# HYDRA_V4_ACTUATOR.net
KiCad netlist of a schematic drawn in Altium Designer
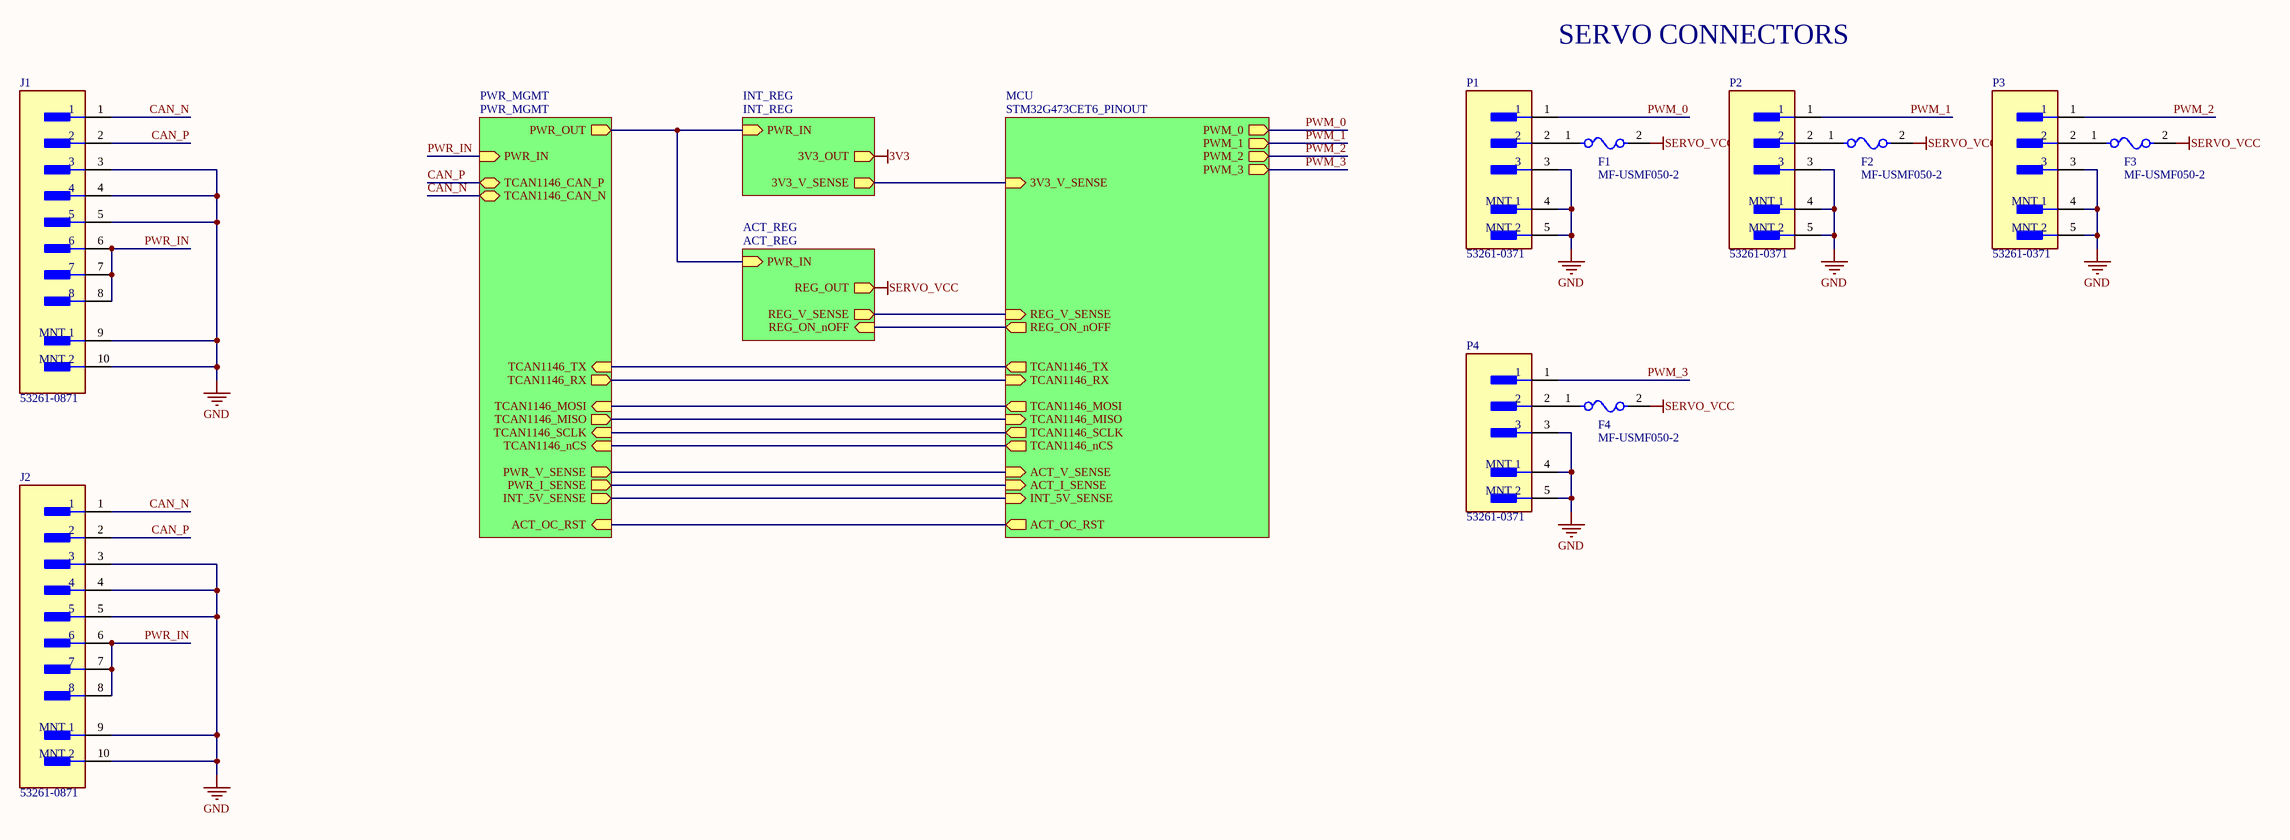
[diagram p0: HYDRA_V4_ACTUATOR.SchDoc]

(export (version "E")
  (design (tool "Eeschema 10.0.6"))
  (components
    (comp (ref "F1")
      (value "MF-USMF050-2")
      (footprint "FP-MF-USMF-MFG")
      (description "PTC RESET FUSE 13.2V 500MA 1210")
      (fields
        (field (name "MANUFACTURER") "Bourns Inc.")
        (field (name "OCTOPART") "https://octopart.com/mf-usmf050-2-bourns-97645")
      )
      (libsource (lib "Altium Content Vault") (part "5bcf9b9f640e542cf0359d10258e979"))
    )
    (comp (ref "F2")
      (value "MF-USMF050-2")
      (footprint "FP-MF-USMF-MFG")
      (description "PTC RESET FUSE 13.2V 500MA 1210")
      (fields
        (field (name "MANUFACTURER") "Bourns Inc.")
        (field (name "OCTOPART") "https://octopart.com/mf-usmf050-2-bourns-97645")
      )
      (libsource (lib "Altium Content Vault") (part "5bcf9b9f640e542cf0359d10258e979"))
    )
    (comp (ref "F3")
      (value "MF-USMF050-2")
      (footprint "FP-MF-USMF-MFG")
      (description "PTC RESET FUSE 13.2V 500MA 1210")
      (fields
        (field (name "MANUFACTURER") "Bourns Inc.")
        (field (name "OCTOPART") "https://octopart.com/mf-usmf050-2-bourns-97645")
      )
      (libsource (lib "Altium Content Vault") (part "5bcf9b9f640e542cf0359d10258e979"))
    )
    (comp (ref "F4")
      (value "MF-USMF050-2")
      (footprint "FP-MF-USMF-MFG")
      (description "PTC RESET FUSE 13.2V 500MA 1210")
      (fields
        (field (name "MANUFACTURER") "Bourns Inc.")
        (field (name "OCTOPART") "https://octopart.com/mf-usmf050-2-bourns-97645")
      )
      (libsource (lib "Altium Content Vault") (part "5bcf9b9f640e542cf0359d10258e979"))
    )
    (comp (ref "J1")
      (value "53261-0871")
      (footprint "FP-532610871-MFG")
      (libsource (lib "Space Concordia") (part "98b5586d6b3804e276fbd0410cd4945"))
    )
    (comp (ref "J2")
      (value "53261-0871")
      (footprint "FP-532610871-MFG")
      (libsource (lib "Space Concordia") (part "98b5586d6b3804e276fbd0410cd4945"))
    )
    (comp (ref "P1")
      (value "53261-0371")
      (footprint "FP-53261-0371-MFG")
      (description "CONN HEADER SMD R/A 3POS 1.25MM")
      (fields
        (field (name "MANUFACTURER") "Molex")
        (field (name "OCTOPART") "https://octopart.com/53261-0371-molex-655314")
      )
      (libsource (lib "Altium Content Vault") (part "13850a6865a90496d8e6d51657cef87"))
    )
    (comp (ref "P2")
      (value "53261-0371")
      (footprint "FP-53261-0371-MFG")
      (description "CONN HEADER SMD R/A 3POS 1.25MM")
      (fields
        (field (name "MANUFACTURER") "Molex")
        (field (name "OCTOPART") "https://octopart.com/53261-0371-molex-655314")
      )
      (libsource (lib "Altium Content Vault") (part "13850a6865a90496d8e6d51657cef87"))
    )
    (comp (ref "P3")
      (value "53261-0371")
      (footprint "FP-53261-0371-MFG")
      (description "CONN HEADER SMD R/A 3POS 1.25MM")
      (fields
        (field (name "MANUFACTURER") "Molex")
        (field (name "OCTOPART") "https://octopart.com/53261-0371-molex-655314")
      )
      (libsource (lib "Altium Content Vault") (part "13850a6865a90496d8e6d51657cef87"))
    )
    (comp (ref "P4")
      (value "53261-0371")
      (footprint "FP-53261-0371-MFG")
      (description "CONN HEADER SMD R/A 3POS 1.25MM")
      (fields
        (field (name "MANUFACTURER") "Molex")
        (field (name "OCTOPART") "https://octopart.com/53261-0371-molex-655314")
      )
      (libsource (lib "Altium Content Vault") (part "13850a6865a90496d8e6d51657cef87"))
    )
  )
  (nets
    (net (code "3") (name "/CAN_N") (class "Default")
      (node (ref "J1") (pin "1") (pinfunction "1_1") (pintype "passive"))
      (node (ref "J2") (pin "1") (pinfunction "1_1") (pintype "passive"))
    )
    (net (code "4") (name "/CAN_P") (class "Default")
      (node (ref "J1") (pin "2") (pinfunction "2_2") (pintype "passive"))
      (node (ref "J2") (pin "2") (pinfunction "2_2") (pintype "passive"))
    )
    (net (code "6") (name "/PWM_0") (class "Default")
      (node (ref "P1") (pin "1") (pinfunction "1_1") (pintype "passive"))
    )
    (net (code "7") (name "/PWM_1") (class "Default")
      (node (ref "P2") (pin "1") (pinfunction "1_1") (pintype "passive"))
    )
    (net (code "8") (name "/PWM_2") (class "Default")
      (node (ref "P3") (pin "1") (pinfunction "1_1") (pintype "passive"))
    )
    (net (code "9") (name "/PWM_3") (class "Default")
      (node (ref "P4") (pin "1") (pinfunction "1_1") (pintype "passive"))
    )
    (net (code "10") (name "/PWR_IN") (class "Default")
      (node (ref "J1") (pin "6") (pinfunction "6_6") (pintype "passive"))
      (node (ref "J1") (pin "7") (pinfunction "7_7") (pintype "passive"))
      (node (ref "J1") (pin "8") (pinfunction "8_8") (pintype "passive"))
      (node (ref "J2") (pin "6") (pinfunction "6_6") (pintype "passive"))
      (node (ref "J2") (pin "7") (pinfunction "7_7") (pintype "passive"))
      (node (ref "J2") (pin "8") (pinfunction "8_8") (pintype "passive"))
    )
    (net (code "23") (name "GND") (class "Default")
      (node (ref "J1") (pin "10") (pinfunction "MNT_2_10") (pintype "passive"))
      (node (ref "J1") (pin "3") (pinfunction "3_3") (pintype "passive"))
      (node (ref "J1") (pin "4") (pinfunction "4_4") (pintype "passive"))
      (node (ref "J1") (pin "5") (pinfunction "5_5") (pintype "passive"))
      (node (ref "J1") (pin "9") (pinfunction "MNT_1_9") (pintype "passive"))
      (node (ref "J2") (pin "10") (pinfunction "MNT_2_10") (pintype "passive"))
      (node (ref "J2") (pin "3") (pinfunction "3_3") (pintype "passive"))
      (node (ref "J2") (pin "4") (pinfunction "4_4") (pintype "passive"))
      (node (ref "J2") (pin "5") (pinfunction "5_5") (pintype "passive"))
      (node (ref "J2") (pin "9") (pinfunction "MNT_1_9") (pintype "passive"))
      (node (ref "P1") (pin "3") (pinfunction "3_3") (pintype "passive"))
      (node (ref "P1") (pin "4") (pinfunction "MNT_1_4") (pintype "passive"))
      (node (ref "P1") (pin "5") (pinfunction "MNT_2_5") (pintype "passive"))
      (node (ref "P2") (pin "3") (pinfunction "3_3") (pintype "passive"))
      (node (ref "P2") (pin "4") (pinfunction "MNT_1_4") (pintype "passive"))
      (node (ref "P2") (pin "5") (pinfunction "MNT_2_5") (pintype "passive"))
      (node (ref "P3") (pin "3") (pinfunction "3_3") (pintype "passive"))
      (node (ref "P3") (pin "4") (pinfunction "MNT_1_4") (pintype "passive"))
      (node (ref "P3") (pin "5") (pinfunction "MNT_2_5") (pintype "passive"))
      (node (ref "P4") (pin "3") (pinfunction "3_3") (pintype "passive"))
      (node (ref "P4") (pin "4") (pinfunction "MNT_1_4") (pintype "passive"))
      (node (ref "P4") (pin "5") (pinfunction "MNT_2_5") (pintype "passive"))
    )
    (net (code "24") (name "Net-(F1-Pad1)") (class "Default")
      (node (ref "F1") (pin "1") (pinfunction "1_1") (pintype "passive"))
      (node (ref "P1") (pin "2") (pinfunction "2_2") (pintype "passive"))
    )
    (net (code "25") (name "Net-(F2-Pad1)") (class "Default")
      (node (ref "F2") (pin "1") (pinfunction "1_1") (pintype "passive"))
      (node (ref "P2") (pin "2") (pinfunction "2_2") (pintype "passive"))
    )
    (net (code "26") (name "Net-(F3-Pad1)") (class "Default")
      (node (ref "F3") (pin "1") (pinfunction "1_1") (pintype "passive"))
      (node (ref "P3") (pin "2") (pinfunction "2_2") (pintype "passive"))
    )
    (net (code "27") (name "Net-(F4-Pad1)") (class "Default")
      (node (ref "F4") (pin "1") (pinfunction "1_1") (pintype "passive"))
      (node (ref "P4") (pin "2") (pinfunction "2_2") (pintype "passive"))
    )
    (net (code "28") (name "SERVO_VCC") (class "Default")
      (node (ref "F1") (pin "2") (pinfunction "2_2") (pintype "passive"))
      (node (ref "F2") (pin "2") (pinfunction "2_2") (pintype "passive"))
      (node (ref "F3") (pin "2") (pinfunction "2_2") (pintype "passive"))
      (node (ref "F4") (pin "2") (pinfunction "2_2") (pintype "passive"))
    )
  )
)
